# Anchor_PCB_V1.net
KiCad netlist of a schematic drawn in EAGLE
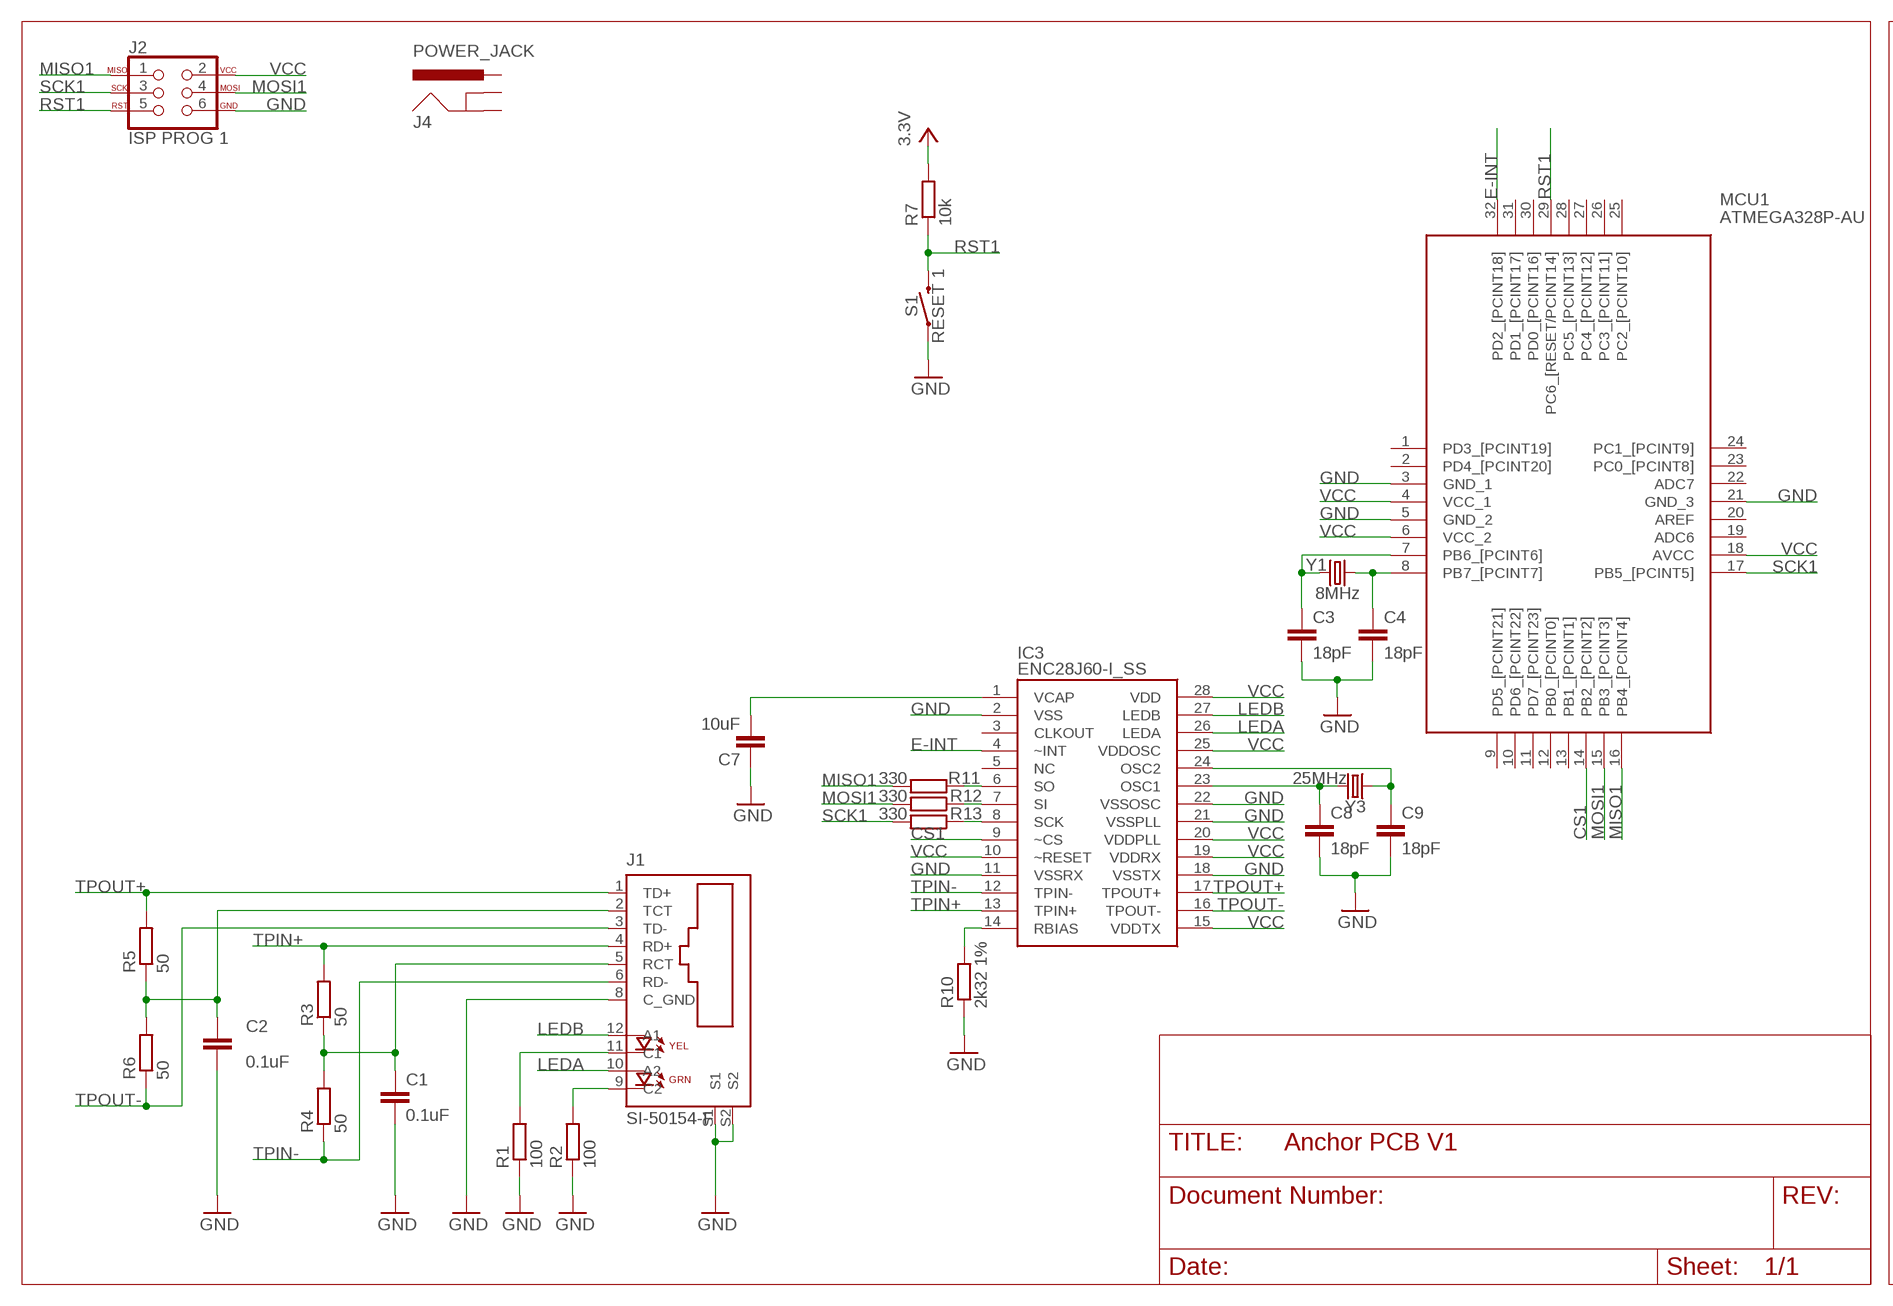
[diagram p0: schematic, sheet 1, part 1 of 2]
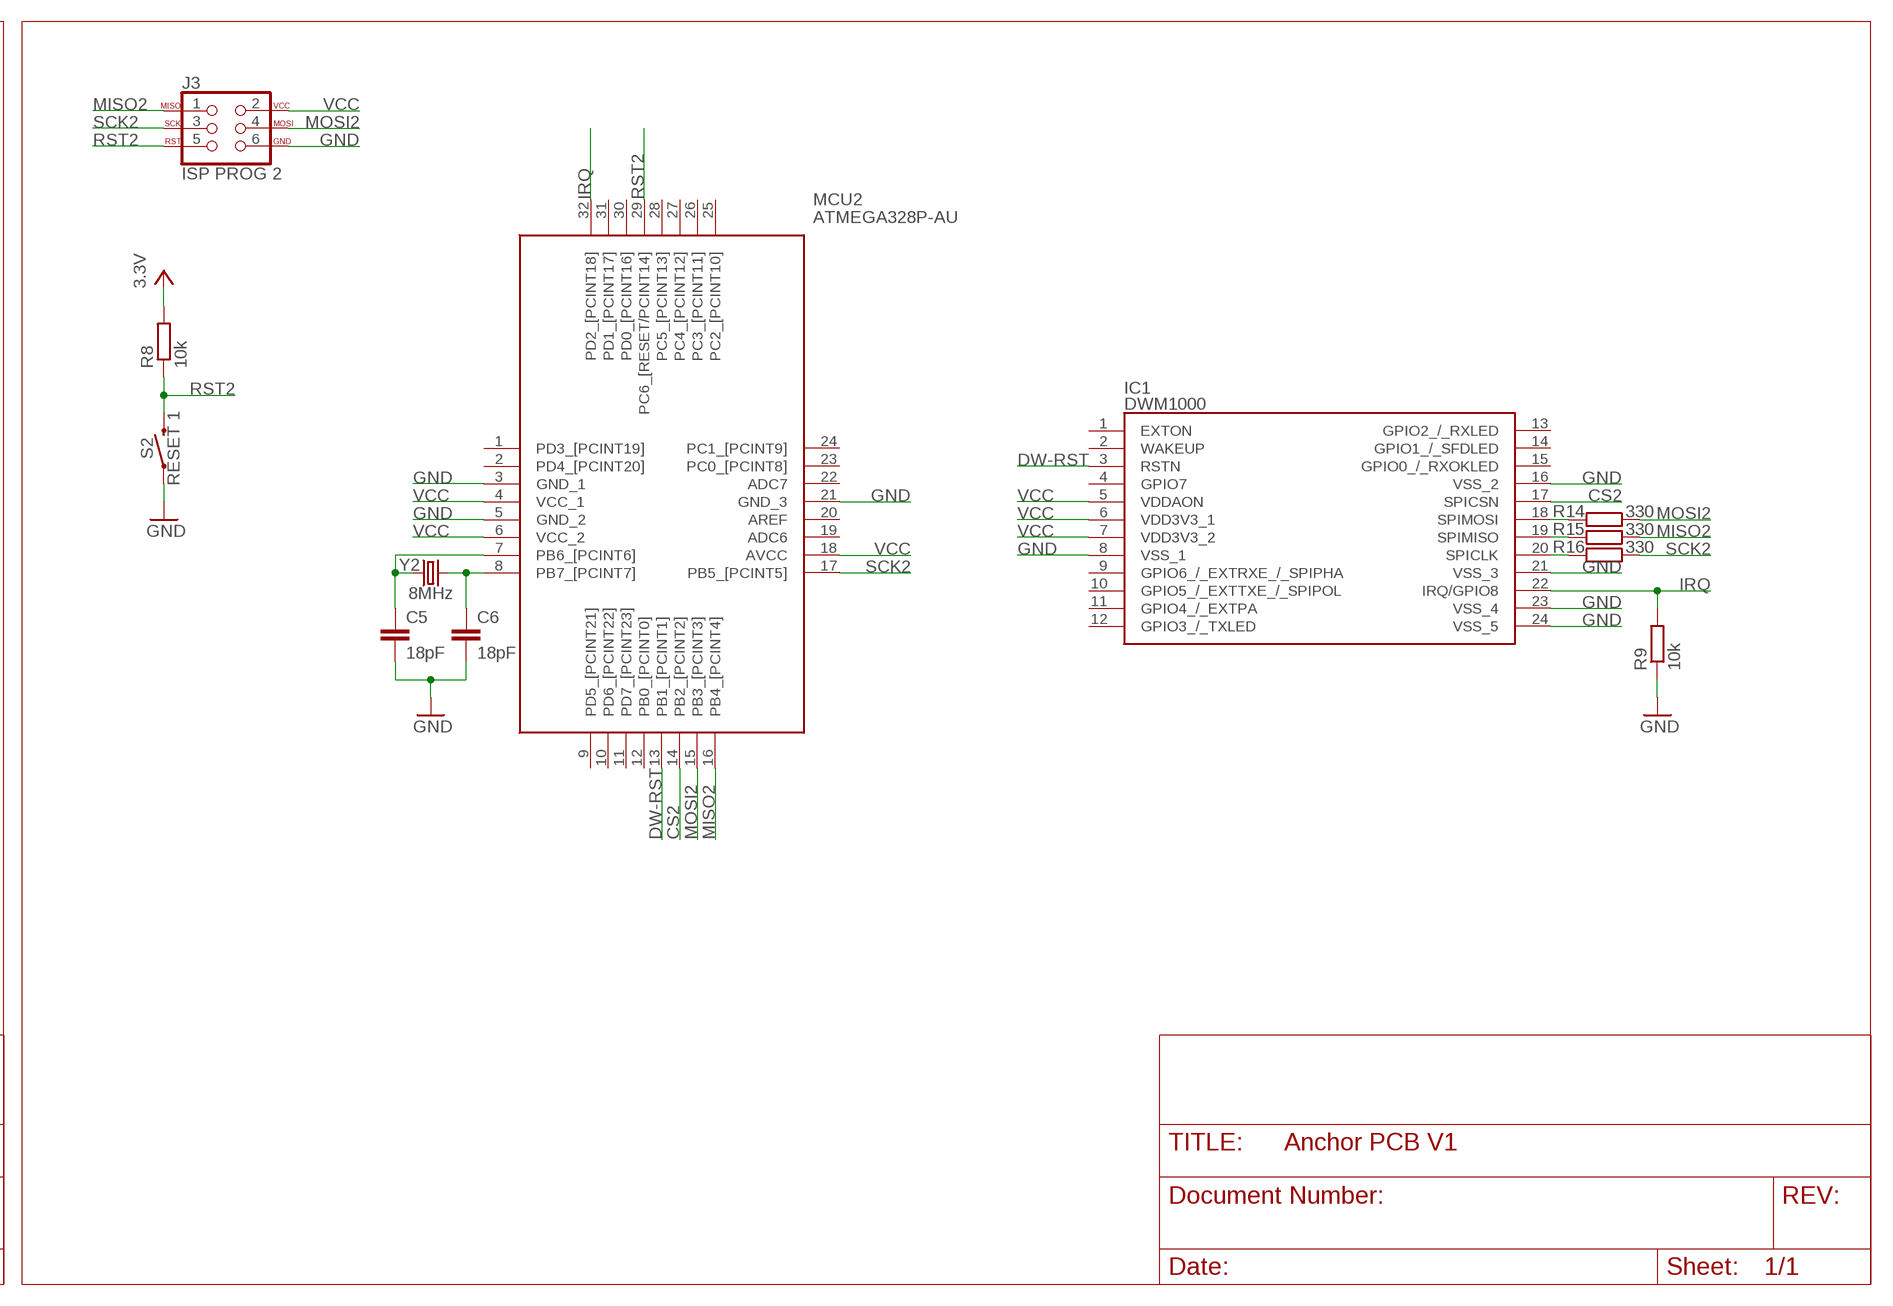
[diagram p1: schematic, sheet 1, part 2 of 2]

(export (version "E")
  (design (tool "Eeschema 10.0.6"))
  (components
    (comp (ref "C1")
      (value "0.1uF")
      (footprint "eagle-import:C1206")
      (libsource (lib "eagle-import") (part "C-EUC1206"))
    )
    (comp (ref "C2")
      (value "0.1uF")
      (footprint "eagle-import:C1206")
      (libsource (lib "eagle-import") (part "C-EUC1206"))
    )
    (comp (ref "C3")
      (value "18pF")
      (footprint "eagle-import:C1206")
      (libsource (lib "eagle-import") (part "C-EUC1206"))
    )
    (comp (ref "C4")
      (value "18pF")
      (footprint "eagle-import:C1206")
      (libsource (lib "eagle-import") (part "C-EUC1206"))
    )
    (comp (ref "C5")
      (value "18pF")
      (footprint "eagle-import:C1206")
      (libsource (lib "eagle-import") (part "C-EUC1206"))
    )
    (comp (ref "C6")
      (value "18pF")
      (footprint "eagle-import:C1206")
      (libsource (lib "eagle-import") (part "C-EUC1206"))
    )
    (comp (ref "C7")
      (value "10uF")
      (footprint "eagle-import:C1206")
      (libsource (lib "eagle-import") (part "C-EUC1206"))
    )
    (comp (ref "C8")
      (value "18pF")
      (footprint "eagle-import:C1206")
      (libsource (lib "eagle-import") (part "C-EUC1206"))
    )
    (comp (ref "C9")
      (value "18pF")
      (footprint "eagle-import:C1206")
      (libsource (lib "eagle-import") (part "C-EUC1206"))
    )
    (comp (ref "IC1")
      (value "DWM1000")
      (footprint "eagle-import:DWM1000")
      (libsource (lib "eagle-import") (part "DWM1000"))
    )
    (comp (ref "IC3")
      (value "ENC28J60-I_SS")
      (footprint "eagle-import:SOP65P780X200-28N")
      (fields (field (name "ARROW_PART_NUMBER") "ENC28J60-I/SS") (field (name "RS_PART_NUMBER") "7707755P"))
      (libsource (lib "eagle-import") (part "ENC28J60-I_SS"))
    )
    (comp (ref "J1")
      (value "SI-50154-F")
      (footprint "eagle-import:STEWART_SI-50154-F")
      (fields (field (name "MF") "Stewart Connector"))
      (libsource (lib "eagle-import") (part "SI-50154-F"))
    )
    (comp (ref "J2")
      (value "ISP PROG 1")
      (footprint "eagle-import:2X3")
      (libsource (lib "eagle-import") (part "AVR_SPI_PROG_3X2PTH"))
    )
    (comp (ref "J3")
      (value "ISP PROG 2")
      (footprint "eagle-import:2X3")
      (libsource (lib "eagle-import") (part "AVR_SPI_PROG_3X2PTH"))
    )
    (comp (ref "J4")
      (value "POWER_JACK")
      (footprint "eagle-import:POWER_JACK_PTH")
      (libsource (lib "eagle-import") (part "POWER_JACK"))
    )
    (comp (ref "MCU1")
      (value "ATMEGA328P-AU")
      (footprint "eagle-import:QFP80P900X900X120-32N")
      (fields (field (name "RS_PART_NUMBER") "1310271"))
      (libsource (lib "eagle-import") (part "ATMEGA328P-AU"))
    )
    (comp (ref "MCU2")
      (value "ATMEGA328P-AU")
      (footprint "eagle-import:QFP80P900X900X120-32N")
      (fields (field (name "RS_PART_NUMBER") "1310271"))
      (libsource (lib "eagle-import") (part "ATMEGA328P-AU"))
    )
    (comp (ref "R1")
      (value "100")
      (footprint "eagle-import:R1206")
      (libsource (lib "eagle-import") (part "R-EU_R1206"))
    )
    (comp (ref "R2")
      (value "100")
      (footprint "eagle-import:R1206")
      (libsource (lib "eagle-import") (part "R-EU_R1206"))
    )
    (comp (ref "R3")
      (value "50")
      (footprint "eagle-import:R1206")
      (libsource (lib "eagle-import") (part "R-EU_R1206"))
    )
    (comp (ref "R4")
      (value "50")
      (footprint "eagle-import:R1206")
      (libsource (lib "eagle-import") (part "R-EU_R1206"))
    )
    (comp (ref "R5")
      (value "50")
      (footprint "eagle-import:R1206")
      (libsource (lib "eagle-import") (part "R-EU_R1206"))
    )
    (comp (ref "R6")
      (value "50")
      (footprint "eagle-import:R1206")
      (libsource (lib "eagle-import") (part "R-EU_R1206"))
    )
    (comp (ref "R7")
      (value "10k")
      (footprint "eagle-import:R1206")
      (libsource (lib "eagle-import") (part "R-EU_R1206"))
    )
    (comp (ref "R8")
      (value "10k")
      (footprint "eagle-import:R1206")
      (libsource (lib "eagle-import") (part "R-EU_R1206"))
    )
    (comp (ref "R9")
      (value "10k")
      (footprint "eagle-import:R1206")
      (libsource (lib "eagle-import") (part "R-EU_R1206"))
    )
    (comp (ref "R10")
      (value "2k32 1%")
      (footprint "eagle-import:R1206")
      (libsource (lib "eagle-import") (part "R-EU_R1206"))
    )
    (comp (ref "R11")
      (value "330")
      (footprint "eagle-import:R1206")
      (libsource (lib "eagle-import") (part "R-EU_R1206"))
    )
    (comp (ref "R12")
      (value "330")
      (footprint "eagle-import:R1206")
      (libsource (lib "eagle-import") (part "R-EU_R1206"))
    )
    (comp (ref "R13")
      (value "330")
      (footprint "eagle-import:R1206")
      (libsource (lib "eagle-import") (part "R-EU_R1206"))
    )
    (comp (ref "R14")
      (value "330")
      (footprint "eagle-import:R1206")
      (libsource (lib "eagle-import") (part "R-EU_R1206"))
    )
    (comp (ref "R15")
      (value "330")
      (footprint "eagle-import:R1206")
      (libsource (lib "eagle-import") (part "R-EU_R1206"))
    )
    (comp (ref "R16")
      (value "330")
      (footprint "eagle-import:R1206")
      (libsource (lib "eagle-import") (part "R-EU_R1206"))
    )
    (comp (ref "S1")
      (value "RESET 1")
      (footprint "eagle-import:TACTILE_SWITCH_PTH_6.0MM")
      (libsource (lib "eagle-import") (part "MOMENTARY-SWITCH-SPST-PTH-6.0MM"))
    )
    (comp (ref "S2")
      (value "RESET 1")
      (footprint "eagle-import:TACTILE_SWITCH_PTH_6.0MM")
      (libsource (lib "eagle-import") (part "MOMENTARY-SWITCH-SPST-PTH-6.0MM"))
    )
    (comp (ref "Y1")
      (value "8MHz")
      (footprint "eagle-import:HC49US")
      (libsource (lib "eagle-import") (part "CRYSTALPTH-HC49US"))
    )
    (comp (ref "Y2")
      (value "8MHz")
      (footprint "eagle-import:HC49US")
      (libsource (lib "eagle-import") (part "CRYSTALPTH-HC49US"))
    )
    (comp (ref "Y3")
      (value "25MHz")
      (footprint "eagle-import:HC49US")
      (libsource (lib "eagle-import") (part "CRYSTALPTH-HC49US"))
    )
  )
  (nets
    (net (code "1") (name "/CS1") (class "Default")
      (node (ref "IC3") (pin "9") (pinfunction "~{CS}_9") (pintype "bidirectional"))
      (node (ref "MCU1") (pin "14") (pinfunction "PB2_[PCINT2]_14") (pintype "bidirectional"))
    )
    (net (code "2") (name "/CS2") (class "Default")
      (node (ref "IC1") (pin "17") (pinfunction "SPICSN_17") (pintype "bidirectional"))
      (node (ref "MCU2") (pin "14") (pinfunction "PB2_[PCINT2]_14") (pintype "bidirectional"))
    )
    (net (code "3") (name "/DW-RST") (class "Default")
      (node (ref "IC1") (pin "3") (pinfunction "RSTN_3") (pintype "bidirectional"))
      (node (ref "MCU2") (pin "13") (pinfunction "PB1_[PCINT1]_13") (pintype "bidirectional"))
    )
    (net (code "4") (name "/E-INT") (class "Default")
      (node (ref "IC3") (pin "4") (pinfunction "~{INT}_4") (pintype "bidirectional"))
      (node (ref "MCU1") (pin "32") (pinfunction "PD2_[PCINT18]_32") (pintype "bidirectional"))
    )
    (net (code "5") (name "/IRQ") (class "Default")
      (node (ref "IC1") (pin "22") (pinfunction "IRQ/GPIO8_22") (pintype "bidirectional"))
      (node (ref "MCU2") (pin "32") (pinfunction "PD2_[PCINT18]_32") (pintype "bidirectional"))
      (node (ref "R9") (pin "2") (pinfunction "2_2") (pintype "passive"))
    )
    (net (code "6") (name "/LEDA") (class "Default")
      (node (ref "IC3") (pin "26") (pinfunction "LEDA_26") (pintype "bidirectional"))
      (node (ref "J1") (pin "10") (pinfunction "A2_10") (pintype "passive"))
    )
    (net (code "7") (name "/LEDB") (class "Default")
      (node (ref "IC3") (pin "27") (pinfunction "LEDB_27") (pintype "bidirectional"))
      (node (ref "J1") (pin "12") (pinfunction "A1_12") (pintype "passive"))
    )
    (net (code "8") (name "/MISO1") (class "Default")
      (node (ref "J2") (pin "1") (pinfunction "1_1") (pintype "passive"))
      (node (ref "MCU1") (pin "16") (pinfunction "PB4_[PCINT4]_16") (pintype "bidirectional"))
      (node (ref "R11") (pin "2") (pinfunction "2_2") (pintype "passive"))
    )
    (net (code "9") (name "/MISO2") (class "Default")
      (node (ref "J3") (pin "1") (pinfunction "1_1") (pintype "passive"))
      (node (ref "MCU2") (pin "16") (pinfunction "PB4_[PCINT4]_16") (pintype "bidirectional"))
      (node (ref "R15") (pin "1") (pinfunction "1_1") (pintype "passive"))
    )
    (net (code "10") (name "/MOSI1") (class "Default")
      (node (ref "J2") (pin "4") (pinfunction "4_4") (pintype "passive"))
      (node (ref "MCU1") (pin "15") (pinfunction "PB3_[PCINT3]_15") (pintype "bidirectional"))
      (node (ref "R12") (pin "2") (pinfunction "2_2") (pintype "passive"))
    )
    (net (code "11") (name "/MOSI2") (class "Default")
      (node (ref "J3") (pin "4") (pinfunction "4_4") (pintype "passive"))
      (node (ref "MCU2") (pin "15") (pinfunction "PB3_[PCINT3]_15") (pintype "bidirectional"))
      (node (ref "R14") (pin "1") (pinfunction "1_1") (pintype "passive"))
    )
    (net (code "12") (name "/RST1") (class "Default")
      (node (ref "J2") (pin "5") (pinfunction "5_5") (pintype "passive"))
      (node (ref "MCU1") (pin "29") (pinfunction "PC6_[RESET/PCINT14]_29") (pintype "bidirectional"))
      (node (ref "R7") (pin "1") (pinfunction "1_1") (pintype "passive"))
      (node (ref "S1") (pin "3") (pinfunction "2_3") (pintype "passive"))
    )
    (net (code "13") (name "/RST2") (class "Default")
      (node (ref "J3") (pin "5") (pinfunction "5_5") (pintype "passive"))
      (node (ref "MCU2") (pin "29") (pinfunction "PC6_[RESET/PCINT14]_29") (pintype "bidirectional"))
      (node (ref "R8") (pin "1") (pinfunction "1_1") (pintype "passive"))
      (node (ref "S2") (pin "3") (pinfunction "2_3") (pintype "passive"))
    )
    (net (code "14") (name "/SCK1") (class "Default")
      (node (ref "J2") (pin "3") (pinfunction "3_3") (pintype "passive"))
      (node (ref "MCU1") (pin "17") (pinfunction "PB5_[PCINT5]_17") (pintype "bidirectional"))
      (node (ref "R13") (pin "2") (pinfunction "2_2") (pintype "passive"))
    )
    (net (code "15") (name "/SCK2") (class "Default")
      (node (ref "J3") (pin "3") (pinfunction "3_3") (pintype "passive"))
      (node (ref "MCU2") (pin "17") (pinfunction "PB5_[PCINT5]_17") (pintype "bidirectional"))
      (node (ref "R16") (pin "1") (pinfunction "1_1") (pintype "passive"))
    )
    (net (code "16") (name "/TPIN+") (class "Default")
      (node (ref "IC3") (pin "13") (pinfunction "TPIN+_13") (pintype "bidirectional"))
      (node (ref "J1") (pin "4") (pinfunction "RD+_4") (pintype "passive"))
      (node (ref "R3") (pin "2") (pinfunction "2_2") (pintype "passive"))
    )
    (net (code "17") (name "/TPIN-") (class "Default")
      (node (ref "IC3") (pin "12") (pinfunction "TPIN-_12") (pintype "bidirectional"))
      (node (ref "J1") (pin "6") (pinfunction "RD-_6") (pintype "passive"))
      (node (ref "R4") (pin "1") (pinfunction "1_1") (pintype "passive"))
    )
    (net (code "18") (name "/TPOUT+") (class "Default")
      (node (ref "IC3") (pin "17") (pinfunction "TPOUT+_17") (pintype "bidirectional"))
      (node (ref "J1") (pin "1") (pinfunction "TD+_1") (pintype "passive"))
      (node (ref "R5") (pin "2") (pinfunction "2_2") (pintype "passive"))
    )
    (net (code "19") (name "/TPOUT-") (class "Default")
      (node (ref "IC3") (pin "16") (pinfunction "TPOUT-_16") (pintype "bidirectional"))
      (node (ref "J1") (pin "3") (pinfunction "TD-_3") (pintype "passive"))
      (node (ref "R6") (pin "1") (pinfunction "1_1") (pintype "passive"))
    )
    (net (code "20") (name "3.3V") (class "Default")
      (node (ref "IC1") (pin "5") (pinfunction "VDDAON_5") (pintype "bidirectional"))
      (node (ref "IC1") (pin "6") (pinfunction "VDD3V3_1_6") (pintype "bidirectional"))
      (node (ref "IC1") (pin "7") (pinfunction "VDD3V3_2_7") (pintype "bidirectional"))
      (node (ref "IC3") (pin "10") (pinfunction "~{RESET}_10") (pintype "bidirectional"))
      (node (ref "IC3") (pin "15") (pinfunction "VDDTX_15") (pintype "bidirectional"))
      (node (ref "IC3") (pin "19") (pinfunction "VDDRX_19") (pintype "bidirectional"))
      (node (ref "IC3") (pin "20") (pinfunction "VDDPLL_20") (pintype "bidirectional"))
      (node (ref "IC3") (pin "25") (pinfunction "VDDOSC_25") (pintype "bidirectional"))
      (node (ref "IC3") (pin "28") (pinfunction "VDD_28") (pintype "bidirectional"))
      (node (ref "J2") (pin "2") (pinfunction "2_2") (pintype "passive"))
      (node (ref "J3") (pin "2") (pinfunction "2_2") (pintype "passive"))
      (node (ref "MCU1") (pin "18") (pinfunction "AVCC_18") (pintype "power_in"))
      (node (ref "MCU1") (pin "4") (pinfunction "VCC_1_4") (pintype "power_in"))
      (node (ref "MCU1") (pin "6") (pinfunction "VCC_2_6") (pintype "power_in"))
      (node (ref "MCU2") (pin "18") (pinfunction "AVCC_18") (pintype "power_in"))
      (node (ref "MCU2") (pin "4") (pinfunction "VCC_1_4") (pintype "power_in"))
      (node (ref "MCU2") (pin "6") (pinfunction "VCC_2_6") (pintype "power_in"))
      (node (ref "R7") (pin "2") (pinfunction "2_2") (pintype "passive"))
      (node (ref "R8") (pin "2") (pinfunction "2_2") (pintype "passive"))
    )
    (net (code "21") (name "GND") (class "Default")
      (node (ref "C1") (pin "2") (pinfunction "2_2") (pintype "passive"))
      (node (ref "C2") (pin "2") (pinfunction "2_2") (pintype "passive"))
      (node (ref "C3") (pin "2") (pinfunction "2_2") (pintype "passive"))
      (node (ref "C4") (pin "2") (pinfunction "2_2") (pintype "passive"))
      (node (ref "C5") (pin "2") (pinfunction "2_2") (pintype "passive"))
      (node (ref "C6") (pin "2") (pinfunction "2_2") (pintype "passive"))
      (node (ref "C7") (pin "1") (pinfunction "1_1") (pintype "passive"))
      (node (ref "C8") (pin "2") (pinfunction "2_2") (pintype "passive"))
      (node (ref "C9") (pin "2") (pinfunction "2_2") (pintype "passive"))
      (node (ref "IC1") (pin "16") (pinfunction "VSS_2_16") (pintype "bidirectional"))
      (node (ref "IC1") (pin "21") (pinfunction "VSS_3_21") (pintype "bidirectional"))
      (node (ref "IC1") (pin "23") (pinfunction "VSS_4_23") (pintype "bidirectional"))
      (node (ref "IC1") (pin "24") (pinfunction "VSS_5_24") (pintype "bidirectional"))
      (node (ref "IC1") (pin "8") (pinfunction "VSS_1_8") (pintype "bidirectional"))
      (node (ref "IC3") (pin "11") (pinfunction "VSSRX_11") (pintype "bidirectional"))
      (node (ref "IC3") (pin "18") (pinfunction "VSSTX_18") (pintype "bidirectional"))
      (node (ref "IC3") (pin "2") (pinfunction "VSS_2") (pintype "bidirectional"))
      (node (ref "IC3") (pin "21") (pinfunction "VSSPLL_21") (pintype "bidirectional"))
      (node (ref "IC3") (pin "22") (pinfunction "VSSOSC_22") (pintype "bidirectional"))
      (node (ref "J1") (pin "8") (pinfunction "C_GND_8") (pintype "passive"))
      (node (ref "J1") (pin "S1") (pinfunction "S1_S1") (pintype "passive"))
      (node (ref "J1") (pin "S2") (pinfunction "S2_S2") (pintype "passive"))
      (node (ref "J2") (pin "6") (pinfunction "6_6") (pintype "passive"))
      (node (ref "J3") (pin "6") (pinfunction "6_6") (pintype "passive"))
      (node (ref "MCU1") (pin "21") (pinfunction "GND_3_21") (pintype "power_in"))
      (node (ref "MCU1") (pin "3") (pinfunction "GND_1_3") (pintype "power_in"))
      (node (ref "MCU1") (pin "5") (pinfunction "GND_2_5") (pintype "power_in"))
      (node (ref "MCU2") (pin "21") (pinfunction "GND_3_21") (pintype "power_in"))
      (node (ref "MCU2") (pin "3") (pinfunction "GND_1_3") (pintype "power_in"))
      (node (ref "MCU2") (pin "5") (pinfunction "GND_2_5") (pintype "power_in"))
      (node (ref "R1") (pin "1") (pinfunction "1_1") (pintype "passive"))
      (node (ref "R10") (pin "1") (pinfunction "1_1") (pintype "passive"))
      (node (ref "R2") (pin "1") (pinfunction "1_1") (pintype "passive"))
      (node (ref "R9") (pin "1") (pinfunction "1_1") (pintype "passive"))
      (node (ref "S1") (pin "1") (pinfunction "1_1") (pintype "passive"))
      (node (ref "S2") (pin "1") (pinfunction "1_1") (pintype "passive"))
    )
    (net (code "22") (name "Net-(IC1-SPICLK)") (class "Default")
      (node (ref "IC1") (pin "20") (pinfunction "SPICLK_20") (pintype "bidirectional"))
      (node (ref "R16") (pin "2") (pinfunction "2_2") (pintype "passive"))
    )
    (net (code "23") (name "Net-(IC1-SPIMISO)") (class "Default")
      (node (ref "IC1") (pin "19") (pinfunction "SPIMISO_19") (pintype "bidirectional"))
      (node (ref "R15") (pin "2") (pinfunction "2_2") (pintype "passive"))
    )
    (net (code "24") (name "Net-(IC1-SPIMOSI)") (class "Default")
      (node (ref "IC1") (pin "18") (pinfunction "SPIMOSI_18") (pintype "bidirectional"))
      (node (ref "R14") (pin "2") (pinfunction "2_2") (pintype "passive"))
    )
    (net (code "25") (name "Net-(IC3-OSC1)") (class "Default")
      (node (ref "C8") (pin "1") (pinfunction "1_1") (pintype "passive"))
      (node (ref "IC3") (pin "23") (pinfunction "OSC1_23") (pintype "bidirectional"))
      (node (ref "Y3") (pin "2") (pinfunction "2_2") (pintype "passive"))
    )
    (net (code "26") (name "Net-(IC3-OSC2)") (class "Default")
      (node (ref "C9") (pin "1") (pinfunction "1_1") (pintype "passive"))
      (node (ref "IC3") (pin "24") (pinfunction "OSC2_24") (pintype "bidirectional"))
      (node (ref "Y3") (pin "1") (pinfunction "1_1") (pintype "passive"))
    )
    (net (code "27") (name "Net-(IC3-RBIAS)") (class "Default")
      (node (ref "IC3") (pin "14") (pinfunction "RBIAS_14") (pintype "bidirectional"))
      (node (ref "R10") (pin "2") (pinfunction "2_2") (pintype "passive"))
    )
    (net (code "28") (name "Net-(IC3-SCK)") (class "Default")
      (node (ref "IC3") (pin "8") (pinfunction "SCK_8") (pintype "bidirectional"))
      (node (ref "R13") (pin "1") (pinfunction "1_1") (pintype "passive"))
    )
    (net (code "29") (name "Net-(IC3-SI)") (class "Default")
      (node (ref "IC3") (pin "7") (pinfunction "SI_7") (pintype "bidirectional"))
      (node (ref "R12") (pin "1") (pinfunction "1_1") (pintype "passive"))
    )
    (net (code "30") (name "Net-(IC3-SO)") (class "Default")
      (node (ref "IC3") (pin "6") (pinfunction "SO_6") (pintype "bidirectional"))
      (node (ref "R11") (pin "1") (pinfunction "1_1") (pintype "passive"))
    )
    (net (code "31") (name "Net-(IC3-VCAP)") (class "Default")
      (node (ref "C7") (pin "2") (pinfunction "2_2") (pintype "passive"))
      (node (ref "IC3") (pin "1") (pinfunction "VCAP_1") (pintype "bidirectional"))
    )
    (net (code "32") (name "Net-(J1-C1)") (class "Default")
      (node (ref "J1") (pin "11") (pinfunction "C1_11") (pintype "passive"))
      (node (ref "R1") (pin "2") (pinfunction "2_2") (pintype "passive"))
    )
    (net (code "33") (name "Net-(J1-C2)") (class "Default")
      (node (ref "J1") (pin "9") (pinfunction "C2_9") (pintype "passive"))
      (node (ref "R2") (pin "2") (pinfunction "2_2") (pintype "passive"))
    )
    (net (code "34") (name "Net-(J1-RCT)") (class "Default")
      (node (ref "C1") (pin "1") (pinfunction "1_1") (pintype "passive"))
      (node (ref "J1") (pin "5") (pinfunction "RCT_5") (pintype "passive"))
      (node (ref "R3") (pin "1") (pinfunction "1_1") (pintype "passive"))
      (node (ref "R4") (pin "2") (pinfunction "2_2") (pintype "passive"))
    )
    (net (code "35") (name "Net-(J1-TCT)") (class "Default")
      (node (ref "C2") (pin "1") (pinfunction "1_1") (pintype "passive"))
      (node (ref "J1") (pin "2") (pinfunction "TCT_2") (pintype "passive"))
      (node (ref "R5") (pin "1") (pinfunction "1_1") (pintype "passive"))
      (node (ref "R6") (pin "2") (pinfunction "2_2") (pintype "passive"))
    )
    (net (code "36") (name "Net-(MCU1-PB6_[PCINT6])") (class "Default")
      (node (ref "C3") (pin "1") (pinfunction "1_1") (pintype "passive"))
      (node (ref "MCU1") (pin "7") (pinfunction "PB6_[PCINT6]_7") (pintype "bidirectional"))
      (node (ref "Y1") (pin "2") (pinfunction "2_2") (pintype "passive"))
    )
    (net (code "37") (name "Net-(MCU1-PB7_[PCINT7])") (class "Default")
      (node (ref "C4") (pin "1") (pinfunction "1_1") (pintype "passive"))
      (node (ref "MCU1") (pin "8") (pinfunction "PB7_[PCINT7]_8") (pintype "bidirectional"))
      (node (ref "Y1") (pin "1") (pinfunction "1_1") (pintype "passive"))
    )
    (net (code "38") (name "Net-(MCU2-PB6_[PCINT6])") (class "Default")
      (node (ref "C5") (pin "1") (pinfunction "1_1") (pintype "passive"))
      (node (ref "MCU2") (pin "7") (pinfunction "PB6_[PCINT6]_7") (pintype "bidirectional"))
      (node (ref "Y2") (pin "1") (pinfunction "1_1") (pintype "passive"))
    )
    (net (code "39") (name "Net-(MCU2-PB7_[PCINT7])") (class "Default")
      (node (ref "C6") (pin "1") (pinfunction "1_1") (pintype "passive"))
      (node (ref "MCU2") (pin "8") (pinfunction "PB7_[PCINT7]_8") (pintype "bidirectional"))
      (node (ref "Y2") (pin "2") (pinfunction "2_2") (pintype "passive"))
    )
    (net (code "40") (name "unconnected-(IC1-EXTON-Pad1)") (class "Default")
      (node (ref "IC1") (pin "1") (pinfunction "EXTON_1") (pintype "bidirectional"))
    )
    (net (code "41") (name "unconnected-(IC1-GPIO0_{slash}_RXOKLED-Pad15)") (class "Default")
      (node (ref "IC1") (pin "15") (pinfunction "GPIO0_/_RXOKLED_15") (pintype "bidirectional"))
    )
    (net (code "42") (name "unconnected-(IC1-GPIO1_{slash}_SFDLED-Pad14)") (class "Default")
      (node (ref "IC1") (pin "14") (pinfunction "GPIO1_/_SFDLED_14") (pintype "bidirectional"))
    )
    (net (code "43") (name "unconnected-(IC1-GPIO2_{slash}_RXLED-Pad13)") (class "Default")
      (node (ref "IC1") (pin "13") (pinfunction "GPIO2_/_RXLED_13") (pintype "bidirectional"))
    )
    (net (code "44") (name "unconnected-(IC1-GPIO3_{slash}_TXLED-Pad12)") (class "Default")
      (node (ref "IC1") (pin "12") (pinfunction "GPIO3_/_TXLED_12") (pintype "bidirectional"))
    )
    (net (code "45") (name "unconnected-(IC1-GPIO4_{slash}_EXTPA-Pad11)") (class "Default")
      (node (ref "IC1") (pin "11") (pinfunction "GPIO4_/_EXTPA_11") (pintype "bidirectional"))
    )
    (net (code "46") (name "unconnected-(IC1-GPIO5_{slash}_EXTTXE_{slash}_SPIPOL-Pad10)") (class "Default")
      (node (ref "IC1") (pin "10") (pinfunction "GPIO5_/_EXTTXE_/_SPIPOL_10") (pintype "bidirectional"))
    )
    (net (code "47") (name "unconnected-(IC1-GPIO6_{slash}_EXTRXE_{slash}_SPIPHA-Pad9)") (class "Default")
      (node (ref "IC1") (pin "9") (pinfunction "GPIO6_/_EXTRXE_/_SPIPHA_9") (pintype "bidirectional"))
    )
    (net (code "48") (name "unconnected-(IC1-GPIO7-Pad4)") (class "Default")
      (node (ref "IC1") (pin "4") (pinfunction "GPIO7_4") (pintype "bidirectional"))
    )
    (net (code "49") (name "unconnected-(IC1-WAKEUP-Pad2)") (class "Default")
      (node (ref "IC1") (pin "2") (pinfunction "WAKEUP_2") (pintype "bidirectional"))
    )
    (net (code "50") (name "unconnected-(IC3-CLKOUT-Pad3)") (class "Default")
      (node (ref "IC3") (pin "3") (pinfunction "CLKOUT_3") (pintype "bidirectional"))
    )
    (net (code "51") (name "unconnected-(IC3-NC-Pad5)") (class "Default")
      (node (ref "IC3") (pin "5") (pinfunction "NC_5") (pintype "no_connect"))
    )
    (net (code "52") (name "unconnected-(J4-PadGND)") (class "Default")
      (node (ref "J4") (pin "GND") (pinfunction "GND_GND") (pintype "bidirectional"))
    )
    (net (code "53") (name "unconnected-(J4-PadGNDBREAK)") (class "Default")
      (node (ref "J4") (pin "GNDBREAK") (pinfunction "GNDBREAK_GNDBREAK") (pintype "bidirectional"))
    )
    (net (code "54") (name "unconnected-(J4-PadPWR)") (class "Default")
      (node (ref "J4") (pin "PWR") (pinfunction "PWR_PWR") (pintype "bidirectional"))
    )
    (net (code "55") (name "unconnected-(MCU1-ADC6-Pad19)") (class "Default")
      (node (ref "MCU1") (pin "19") (pinfunction "ADC6_19") (pintype "bidirectional"))
    )
    (net (code "56") (name "unconnected-(MCU1-ADC7-Pad22)") (class "Default")
      (node (ref "MCU1") (pin "22") (pinfunction "ADC7_22") (pintype "bidirectional"))
    )
    (net (code "57") (name "unconnected-(MCU1-AREF-Pad20)") (class "Default")
      (node (ref "MCU1") (pin "20") (pinfunction "AREF_20") (pintype "bidirectional"))
    )
    (net (code "58") (name "unconnected-(MCU1-PB0_[PCINT0]-Pad12)") (class "Default")
      (node (ref "MCU1") (pin "12") (pinfunction "PB0_[PCINT0]_12") (pintype "bidirectional"))
    )
    (net (code "59") (name "unconnected-(MCU1-PB1_[PCINT1]-Pad13)") (class "Default")
      (node (ref "MCU1") (pin "13") (pinfunction "PB1_[PCINT1]_13") (pintype "bidirectional"))
    )
    (net (code "60") (name "unconnected-(MCU1-PC0_[PCINT8]-Pad23)") (class "Default")
      (node (ref "MCU1") (pin "23") (pinfunction "PC0_[PCINT8]_23") (pintype "bidirectional"))
    )
    (net (code "61") (name "unconnected-(MCU1-PC1_[PCINT9]-Pad24)") (class "Default")
      (node (ref "MCU1") (pin "24") (pinfunction "PC1_[PCINT9]_24") (pintype "bidirectional"))
    )
    (net (code "62") (name "unconnected-(MCU1-PC2_[PCINT10]-Pad25)") (class "Default")
      (node (ref "MCU1") (pin "25") (pinfunction "PC2_[PCINT10]_25") (pintype "bidirectional"))
    )
    (net (code "63") (name "unconnected-(MCU1-PC3_[PCINT11]-Pad26)") (class "Default")
      (node (ref "MCU1") (pin "26") (pinfunction "PC3_[PCINT11]_26") (pintype "bidirectional"))
    )
    (net (code "64") (name "unconnected-(MCU1-PC4_[PCINT12]-Pad27)") (class "Default")
      (node (ref "MCU1") (pin "27") (pinfunction "PC4_[PCINT12]_27") (pintype "bidirectional"))
    )
    (net (code "65") (name "unconnected-(MCU1-PC5_[PCINT13]-Pad28)") (class "Default")
      (node (ref "MCU1") (pin "28") (pinfunction "PC5_[PCINT13]_28") (pintype "bidirectional"))
    )
    (net (code "66") (name "unconnected-(MCU1-PD0_[PCINT16]-Pad30)") (class "Default")
      (node (ref "MCU1") (pin "30") (pinfunction "PD0_[PCINT16]_30") (pintype "bidirectional"))
    )
    (net (code "67") (name "unconnected-(MCU1-PD1_[PCINT17]-Pad31)") (class "Default")
      (node (ref "MCU1") (pin "31") (pinfunction "PD1_[PCINT17]_31") (pintype "bidirectional"))
    )
    (net (code "68") (name "unconnected-(MCU1-PD3_[PCINT19]-Pad1)") (class "Default")
      (node (ref "MCU1") (pin "1") (pinfunction "PD3_[PCINT19]_1") (pintype "bidirectional"))
    )
    (net (code "69") (name "unconnected-(MCU1-PD4_[PCINT20]-Pad2)") (class "Default")
      (node (ref "MCU1") (pin "2") (pinfunction "PD4_[PCINT20]_2") (pintype "bidirectional"))
    )
    (net (code "70") (name "unconnected-(MCU1-PD5_[PCINT21]-Pad9)") (class "Default")
      (node (ref "MCU1") (pin "9") (pinfunction "PD5_[PCINT21]_9") (pintype "bidirectional"))
    )
    (net (code "71") (name "unconnected-(MCU1-PD6_[PCINT22]-Pad10)") (class "Default")
      (node (ref "MCU1") (pin "10") (pinfunction "PD6_[PCINT22]_10") (pintype "bidirectional"))
    )
    (net (code "72") (name "unconnected-(MCU1-PD7_[PCINT23]-Pad11)") (class "Default")
      (node (ref "MCU1") (pin "11") (pinfunction "PD7_[PCINT23]_11") (pintype "bidirectional"))
    )
    (net (code "73") (name "unconnected-(MCU2-ADC6-Pad19)") (class "Default")
      (node (ref "MCU2") (pin "19") (pinfunction "ADC6_19") (pintype "bidirectional"))
    )
    (net (code "74") (name "unconnected-(MCU2-ADC7-Pad22)") (class "Default")
      (node (ref "MCU2") (pin "22") (pinfunction "ADC7_22") (pintype "bidirectional"))
    )
    (net (code "75") (name "unconnected-(MCU2-AREF-Pad20)") (class "Default")
      (node (ref "MCU2") (pin "20") (pinfunction "AREF_20") (pintype "bidirectional"))
    )
    (net (code "76") (name "unconnected-(MCU2-PB0_[PCINT0]-Pad12)") (class "Default")
      (node (ref "MCU2") (pin "12") (pinfunction "PB0_[PCINT0]_12") (pintype "bidirectional"))
    )
    (net (code "77") (name "unconnected-(MCU2-PC0_[PCINT8]-Pad23)") (class "Default")
      (node (ref "MCU2") (pin "23") (pinfunction "PC0_[PCINT8]_23") (pintype "bidirectional"))
    )
    (net (code "78") (name "unconnected-(MCU2-PC1_[PCINT9]-Pad24)") (class "Default")
      (node (ref "MCU2") (pin "24") (pinfunction "PC1_[PCINT9]_24") (pintype "bidirectional"))
    )
    (net (code "79") (name "unconnected-(MCU2-PC2_[PCINT10]-Pad25)") (class "Default")
      (node (ref "MCU2") (pin "25") (pinfunction "PC2_[PCINT10]_25") (pintype "bidirectional"))
    )
    (net (code "80") (name "unconnected-(MCU2-PC3_[PCINT11]-Pad26)") (class "Default")
      (node (ref "MCU2") (pin "26") (pinfunction "PC3_[PCINT11]_26") (pintype "bidirectional"))
    )
    (net (code "81") (name "unconnected-(MCU2-PC4_[PCINT12]-Pad27)") (class "Default")
      (node (ref "MCU2") (pin "27") (pinfunction "PC4_[PCINT12]_27") (pintype "bidirectional"))
    )
    (net (code "82") (name "unconnected-(MCU2-PC5_[PCINT13]-Pad28)") (class "Default")
      (node (ref "MCU2") (pin "28") (pinfunction "PC5_[PCINT13]_28") (pintype "bidirectional"))
    )
    (net (code "83") (name "unconnected-(MCU2-PD0_[PCINT16]-Pad30)") (class "Default")
      (node (ref "MCU2") (pin "30") (pinfunction "PD0_[PCINT16]_30") (pintype "bidirectional"))
    )
    (net (code "84") (name "unconnected-(MCU2-PD1_[PCINT17]-Pad31)") (class "Default")
      (node (ref "MCU2") (pin "31") (pinfunction "PD1_[PCINT17]_31") (pintype "bidirectional"))
    )
    (net (code "85") (name "unconnected-(MCU2-PD3_[PCINT19]-Pad1)") (class "Default")
      (node (ref "MCU2") (pin "1") (pinfunction "PD3_[PCINT19]_1") (pintype "bidirectional"))
    )
    (net (code "86") (name "unconnected-(MCU2-PD4_[PCINT20]-Pad2)") (class "Default")
      (node (ref "MCU2") (pin "2") (pinfunction "PD4_[PCINT20]_2") (pintype "bidirectional"))
    )
    (net (code "87") (name "unconnected-(MCU2-PD5_[PCINT21]-Pad9)") (class "Default")
      (node (ref "MCU2") (pin "9") (pinfunction "PD5_[PCINT21]_9") (pintype "bidirectional"))
    )
    (net (code "88") (name "unconnected-(MCU2-PD6_[PCINT22]-Pad10)") (class "Default")
      (node (ref "MCU2") (pin "10") (pinfunction "PD6_[PCINT22]_10") (pintype "bidirectional"))
    )
    (net (code "89") (name "unconnected-(MCU2-PD7_[PCINT23]-Pad11)") (class "Default")
      (node (ref "MCU2") (pin "11") (pinfunction "PD7_[PCINT23]_11") (pintype "bidirectional"))
    )
  )
)
